# 00A-054.net
KiCad netlist of a schematic drawn in EAGLE
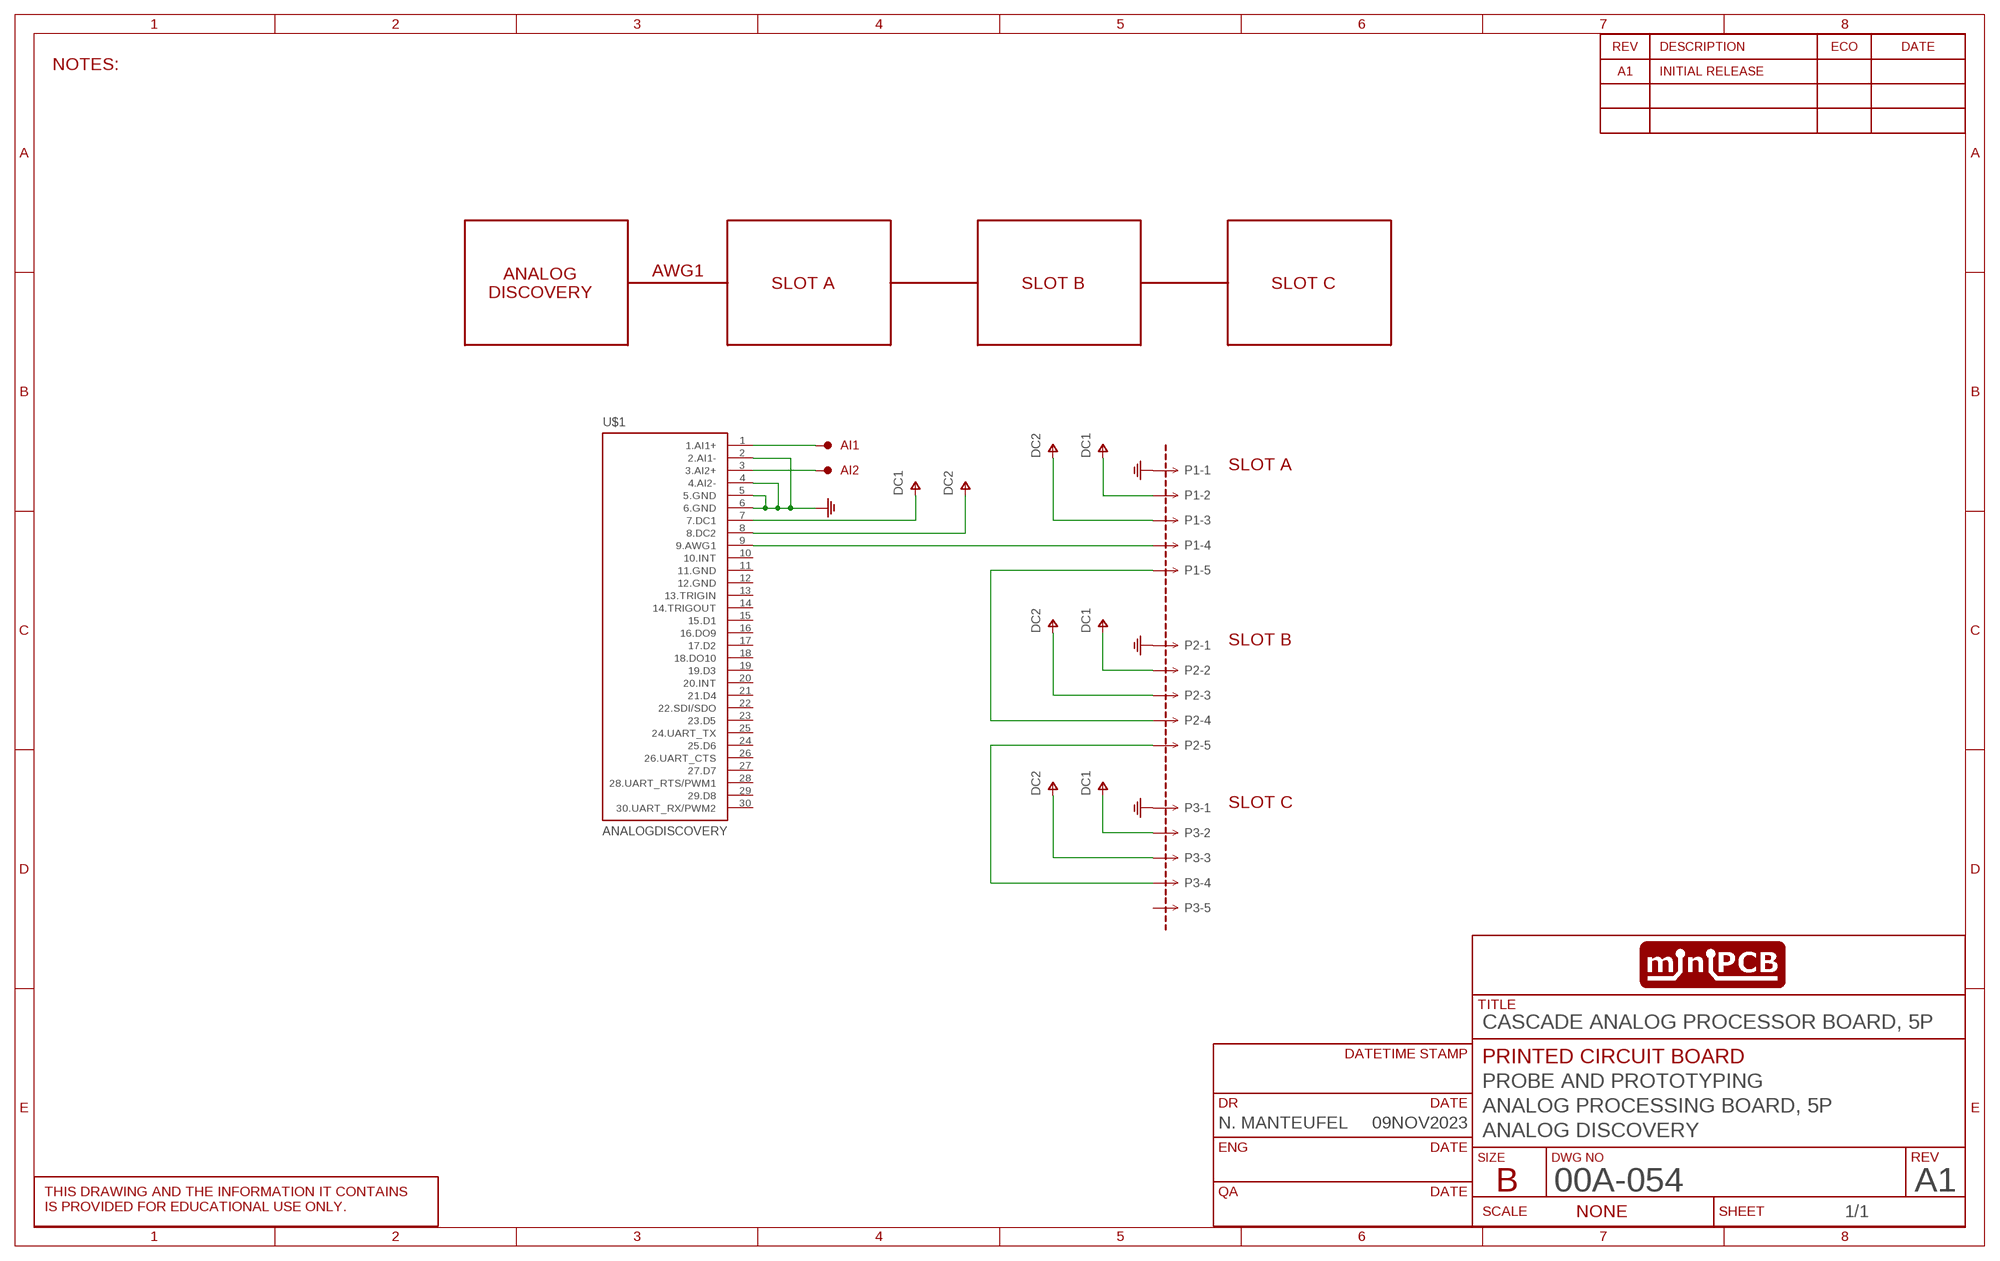
[diagram p0: schematic, sheet 1]

(export (version "E")
  (design (tool "Eeschema 10.0.6"))
  (components
    (comp (ref "AI1")
      (value "TESTPOINTKE5000-SMTEXT")
      (footprint "eagle-import:PINS_1_TESTPOINT_KE5000_NOTEXT")
      (libsource (lib "eagle-import") (part "TESTPOINTKE5000-SMTEXT"))
    )
    (comp (ref "AI2")
      (value "TESTPOINTKE5000-SMTEXT")
      (footprint "eagle-import:PINS_1_TESTPOINT_KE5000_NOTEXT")
      (libsource (lib "eagle-import") (part "TESTPOINTKE5000-SMTEXT"))
    )
    (comp (ref "P1")
      (value "MINIPCB_5P5P")
      (footprint "eagle-import:PINS_1X5")
      (libsource (lib "eagle-import") (part "MINIPCB_5P5P"))
    )
    (comp (ref "P2")
      (value "MINIPCB_5P5P")
      (footprint "eagle-import:PINS_1X5")
      (libsource (lib "eagle-import") (part "MINIPCB_5P5P"))
    )
    (comp (ref "P3")
      (value "MINIPCB_5P5P")
      (footprint "eagle-import:PINS_1X5")
      (libsource (lib "eagle-import") (part "MINIPCB_5P5P"))
    )
    (comp (ref "PCB1")
      (value "MINIPCB_0P33X75")
      (footprint "eagle-import:MINIPCB_0P_33X75")
      (fields
        (field (name "CIRCUIT_CATEGORY") "PROBE AND PROTOTYPING")
        (field (name "PART_NUMBER") "00A-054")
        (field (name "REVISION") "A1-01")
        (field (name "TITLE") "CASCADE ANALOG PROCESSOR BOARD, 5P")
      )
      (libsource (lib "eagle-import") (part "MINIPCB_0P33X75"))
    )
    (comp (ref "U$1")
      (value "ANALOGDISCOVERY")
      (footprint "eagle-import:PINS30-2X15")
      (libsource (lib "eagle-import") (part "ANALOGDISCOVERY"))
    )
  )
  (nets
    (net (code "1") (name "DC1") (class "Default")
      (node (ref "P1") (pin "2") (pinfunction "1_2") (pintype "bidirectional"))
      (node (ref "P1") (pin "3") (pinfunction "1_3") (pintype "bidirectional"))
      (node (ref "P2") (pin "2") (pinfunction "1_2") (pintype "bidirectional"))
      (node (ref "P2") (pin "3") (pinfunction "1_3") (pintype "bidirectional"))
      (node (ref "P3") (pin "2") (pinfunction "1_2") (pintype "bidirectional"))
      (node (ref "P3") (pin "3") (pinfunction "1_3") (pintype "bidirectional"))
      (node (ref "U$1") (pin "7") (pinfunction "7.DC1_7") (pintype "bidirectional"))
      (node (ref "U$1") (pin "8") (pinfunction "8.DC2_8") (pintype "bidirectional"))
    )
    (net (code "2") (name "GND") (class "Default")
      (node (ref "P1") (pin "1") (pinfunction "1_1") (pintype "bidirectional"))
      (node (ref "P2") (pin "1") (pinfunction "1_1") (pintype "bidirectional"))
      (node (ref "P3") (pin "1") (pinfunction "1_1") (pintype "bidirectional"))
      (node (ref "U$1") (pin "2") (pinfunction "2.AI1-_2") (pintype "bidirectional"))
      (node (ref "U$1") (pin "4") (pinfunction "4.AI2-_4") (pintype "bidirectional"))
      (node (ref "U$1") (pin "5") (pinfunction "5.GND_5") (pintype "bidirectional"))
      (node (ref "U$1") (pin "6") (pinfunction "6.GND_6") (pintype "bidirectional"))
    )
    (net (code "3") (name "Net-(P1D-1)") (class "Default")
      (node (ref "P1") (pin "4") (pinfunction "1_4") (pintype "bidirectional"))
      (node (ref "U$1") (pin "9") (pinfunction "9.AWG1_9") (pintype "bidirectional"))
    )
    (net (code "4") (name "Net-(P1E-1)") (class "Default")
      (node (ref "P1") (pin "5") (pinfunction "1_5") (pintype "bidirectional"))
      (node (ref "P2") (pin "4") (pinfunction "1_4") (pintype "bidirectional"))
    )
    (net (code "5") (name "Net-(P2E-1)") (class "Default")
      (node (ref "P2") (pin "5") (pinfunction "1_5") (pintype "bidirectional"))
      (node (ref "P3") (pin "4") (pinfunction "1_4") (pintype "bidirectional"))
    )
    (net (code "6") (name "Net-(U$1-1.AI1+)") (class "Default")
      (node (ref "AI1") (pin "1") (pinfunction "1_1") (pintype "bidirectional"))
      (node (ref "U$1") (pin "1") (pinfunction "1.AI1+_1") (pintype "bidirectional"))
    )
    (net (code "7") (name "Net-(U$1-3.AI2+)") (class "Default")
      (node (ref "AI2") (pin "1") (pinfunction "1_1") (pintype "bidirectional"))
      (node (ref "U$1") (pin "3") (pinfunction "3.AI2+_3") (pintype "bidirectional"))
    )
    (net (code "8") (name "unconnected-(P3E-1-Pad5)") (class "Default")
      (node (ref "P3") (pin "5") (pinfunction "1_5") (pintype "bidirectional"))
    )
    (net (code "9") (name "unconnected-(U$1-10.INT-Pad10)") (class "Default")
      (node (ref "U$1") (pin "10") (pinfunction "10.INT_10") (pintype "bidirectional"))
    )
    (net (code "10") (name "unconnected-(U$1-11.GND-Pad11)") (class "Default")
      (node (ref "U$1") (pin "11") (pinfunction "11.GND_11") (pintype "bidirectional"))
    )
    (net (code "11") (name "unconnected-(U$1-12.GND-Pad12)") (class "Default")
      (node (ref "U$1") (pin "12") (pinfunction "12.GND_12") (pintype "bidirectional"))
    )
    (net (code "12") (name "unconnected-(U$1-13.TRIGIN-Pad13)") (class "Default")
      (node (ref "U$1") (pin "13") (pinfunction "13.TRIGIN_13") (pintype "bidirectional"))
    )
    (net (code "13") (name "unconnected-(U$1-14.TRIGOUT-Pad14)") (class "Default")
      (node (ref "U$1") (pin "14") (pinfunction "14.TRIGOUT_14") (pintype "bidirectional"))
    )
    (net (code "14") (name "unconnected-(U$1-15.D1-Pad15)") (class "Default")
      (node (ref "U$1") (pin "15") (pinfunction "15.D1_15") (pintype "bidirectional"))
    )
    (net (code "15") (name "unconnected-(U$1-16.DO9-Pad16)") (class "Default")
      (node (ref "U$1") (pin "16") (pinfunction "16.DO9_16") (pintype "bidirectional"))
    )
    (net (code "16") (name "unconnected-(U$1-17.D2-Pad17)") (class "Default")
      (node (ref "U$1") (pin "17") (pinfunction "17.D2_17") (pintype "bidirectional"))
    )
    (net (code "17") (name "unconnected-(U$1-18.DO10-Pad18)") (class "Default")
      (node (ref "U$1") (pin "18") (pinfunction "18.DO10_18") (pintype "bidirectional"))
    )
    (net (code "18") (name "unconnected-(U$1-19.D3-Pad19)") (class "Default")
      (node (ref "U$1") (pin "19") (pinfunction "19.D3_19") (pintype "bidirectional"))
    )
    (net (code "19") (name "unconnected-(U$1-20.INT-Pad20)") (class "Default")
      (node (ref "U$1") (pin "20") (pinfunction "20.INT_20") (pintype "bidirectional"))
    )
    (net (code "20") (name "unconnected-(U$1-21.D4-Pad21)") (class "Default")
      (node (ref "U$1") (pin "21") (pinfunction "21.D4_21") (pintype "bidirectional"))
    )
    (net (code "21") (name "unconnected-(U$1-22.SDI{slash}SDO-Pad22)") (class "Default")
      (node (ref "U$1") (pin "22") (pinfunction "22.SDI/SDO_22") (pintype "bidirectional"))
    )
    (net (code "22") (name "unconnected-(U$1-23.D5-Pad23)") (class "Default")
      (node (ref "U$1") (pin "23") (pinfunction "23.D5_23") (pintype "bidirectional"))
    )
    (net (code "23") (name "unconnected-(U$1-24.UART_TX-Pad25)") (class "Default")
      (node (ref "U$1") (pin "25") (pinfunction "24.UART_TX_25") (pintype "bidirectional"))
    )
    (net (code "24") (name "unconnected-(U$1-25.D6-Pad24)") (class "Default")
      (node (ref "U$1") (pin "24") (pinfunction "25.D6_24") (pintype "bidirectional"))
    )
    (net (code "25") (name "unconnected-(U$1-26.UART_CTS-Pad26)") (class "Default")
      (node (ref "U$1") (pin "26") (pinfunction "26.UART_CTS_26") (pintype "bidirectional"))
    )
    (net (code "26") (name "unconnected-(U$1-27.D7-Pad27)") (class "Default")
      (node (ref "U$1") (pin "27") (pinfunction "27.D7_27") (pintype "bidirectional"))
    )
    (net (code "27") (name "unconnected-(U$1-28.UART_RTS{slash}PWM1-Pad28)") (class "Default")
      (node (ref "U$1") (pin "28") (pinfunction "28.UART_RTS/PWM1_28") (pintype "bidirectional"))
    )
    (net (code "28") (name "unconnected-(U$1-29.D8-Pad29)") (class "Default")
      (node (ref "U$1") (pin "29") (pinfunction "29.D8_29") (pintype "bidirectional"))
    )
    (net (code "29") (name "unconnected-(U$1-30.UART_RX{slash}PWM2-Pad30)") (class "Default")
      (node (ref "U$1") (pin "30") (pinfunction "30.UART_RX/PWM2_30") (pintype "bidirectional"))
    )
  )
)
